# SHDN21-S02-V00-SegInterface.net
KiCad netlist of a schematic drawn in Altium Designer
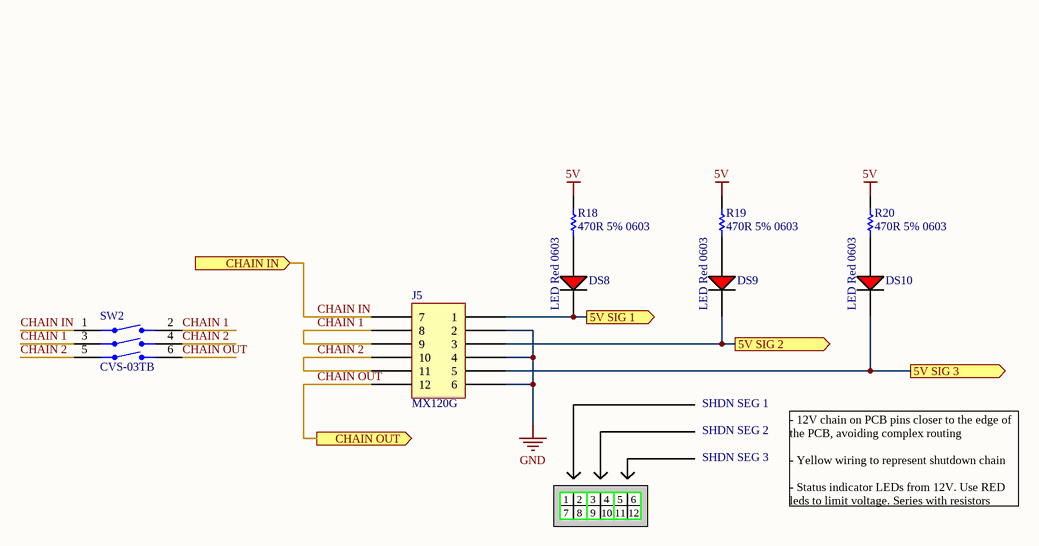
[diagram p0: SHDN21-S02-V00-SegInterface.SchDoc]

(export (version "E")
  (design (tool "Eeschema 10.0.6"))
  (components
    (comp (ref "DS8")
      (value "LED Red 0603")
      (footprint "LED RED 0603")
      (libsource (lib "QUTMS_LEDLibrary") (part "LED Red 0603"))
    )
    (comp (ref "DS9")
      (value "LED Red 0603")
      (footprint "LED RED 0603")
      (libsource (lib "QUTMS_LEDLibrary") (part "LED Red 0603"))
    )
    (comp (ref "DS10")
      (value "LED Red 0603")
      (footprint "LED RED 0603")
      (libsource (lib "QUTMS_LEDLibrary") (part "LED Red 0603"))
    )
    (comp (ref "J5")
      (value "MX120G")
      (footprint "MX120G")
      (description "MX120G with standard connector layout")
      (libsource (lib "QUTMS_MolexLibrary") (part "MX120G"))
    )
    (comp (ref "R18")
      (value "470R 5% 0603")
      (footprint "Res_ThinFilm_0603")
      (description "Resistor, SMD, 470R, 0.1W, 5%, 0603")
      (libsource (lib "StandardResistors") (part "470R 5% 0603"))
    )
    (comp (ref "R19")
      (value "470R 5% 0603")
      (footprint "Res_ThinFilm_0603")
      (description "Resistor, SMD, 470R, 0.1W, 5%, 0603")
      (libsource (lib "StandardResistors") (part "470R 5% 0603"))
    )
    (comp (ref "R20")
      (value "470R 5% 0603")
      (footprint "Res_ThinFilm_0603")
      (description "Resistor, SMD, 470R, 0.1W, 5%, 0603")
      (libsource (lib "StandardResistors") (part "470R 5% 0603"))
    )
    (comp (ref "SW2")
      (value "CVS-03TB")
      (footprint "CVS-03TB")
      (description "SWITCH SLIDE DIP SPST 100MA 6V")
      (libsource (lib "QUTMS_SwitchLibrary") (part "CVS-03TB"))
    )
  )
  (nets
    (net (code "1") (name "/5V SIG 1") (class "Default")
      (node (ref "DS8") (pin "2") (pinfunction "C_2") (pintype "passive"))
      (node (ref "J5") (pin "1") (pinfunction "1_1") (pintype "passive"))
    )
    (net (code "2") (name "/5V SIG 2") (class "Default")
      (node (ref "DS9") (pin "2") (pinfunction "C_2") (pintype "passive"))
      (node (ref "J5") (pin "3") (pinfunction "3_3") (pintype "passive"))
    )
    (net (code "3") (name "/5V SIG 3") (class "Default")
      (node (ref "DS10") (pin "2") (pinfunction "C_2") (pintype "passive"))
      (node (ref "J5") (pin "5") (pinfunction "5_5") (pintype "passive"))
    )
    (net (code "4") (name "/CHAIN 1") (class "Default")
      (node (ref "J5") (pin "8") (pinfunction "8_8") (pintype "passive"))
      (node (ref "J5") (pin "9") (pinfunction "9_9") (pintype "passive"))
      (node (ref "SW2") (pin "2") (pinfunction "2_2") (pintype "passive"))
      (node (ref "SW2") (pin "3") (pinfunction "3_3") (pintype "passive"))
    )
    (net (code "5") (name "/CHAIN 2") (class "Default")
      (node (ref "J5") (pin "10") (pinfunction "10_10") (pintype "passive"))
      (node (ref "J5") (pin "11") (pinfunction "11_11") (pintype "passive"))
      (node (ref "SW2") (pin "4") (pinfunction "4_4") (pintype "passive"))
      (node (ref "SW2") (pin "5") (pinfunction "5_5") (pintype "passive"))
    )
    (net (code "6") (name "/CHAIN IN") (class "Default")
      (node (ref "J5") (pin "7") (pinfunction "7_7") (pintype "passive"))
      (node (ref "SW2") (pin "1") (pinfunction "1_1") (pintype "passive"))
    )
    (net (code "7") (name "/CHAIN OUT") (class "Default")
      (node (ref "J5") (pin "12") (pinfunction "12_12") (pintype "passive"))
      (node (ref "SW2") (pin "6") (pinfunction "6_6") (pintype "passive"))
    )
    (net (code "8") (name "5V") (class "Default")
      (node (ref "R18") (pin "2") (pinfunction "2_2") (pintype "passive"))
      (node (ref "R19") (pin "2") (pinfunction "2_2") (pintype "passive"))
      (node (ref "R20") (pin "2") (pinfunction "2_2") (pintype "passive"))
    )
    (net (code "9") (name "GND") (class "Default")
      (node (ref "J5") (pin "2") (pinfunction "2_2") (pintype "passive"))
      (node (ref "J5") (pin "4") (pinfunction "4_4") (pintype "passive"))
      (node (ref "J5") (pin "6") (pinfunction "6_6") (pintype "passive"))
    )
    (net (code "10") (name "Net-(DS8-A)") (class "Default")
      (node (ref "DS8") (pin "1") (pinfunction "A_1") (pintype "passive"))
      (node (ref "R18") (pin "1") (pinfunction "1_1") (pintype "passive"))
    )
    (net (code "11") (name "Net-(DS9-A)") (class "Default")
      (node (ref "DS9") (pin "1") (pinfunction "A_1") (pintype "passive"))
      (node (ref "R19") (pin "1") (pinfunction "1_1") (pintype "passive"))
    )
    (net (code "12") (name "Net-(DS10-A)") (class "Default")
      (node (ref "DS10") (pin "1") (pinfunction "A_1") (pintype "passive"))
      (node (ref "R20") (pin "1") (pinfunction "1_1") (pintype "passive"))
    )
  )
)
